# fpga-bank0.net
KiCad netlist of a schematic drawn in Altium Designer
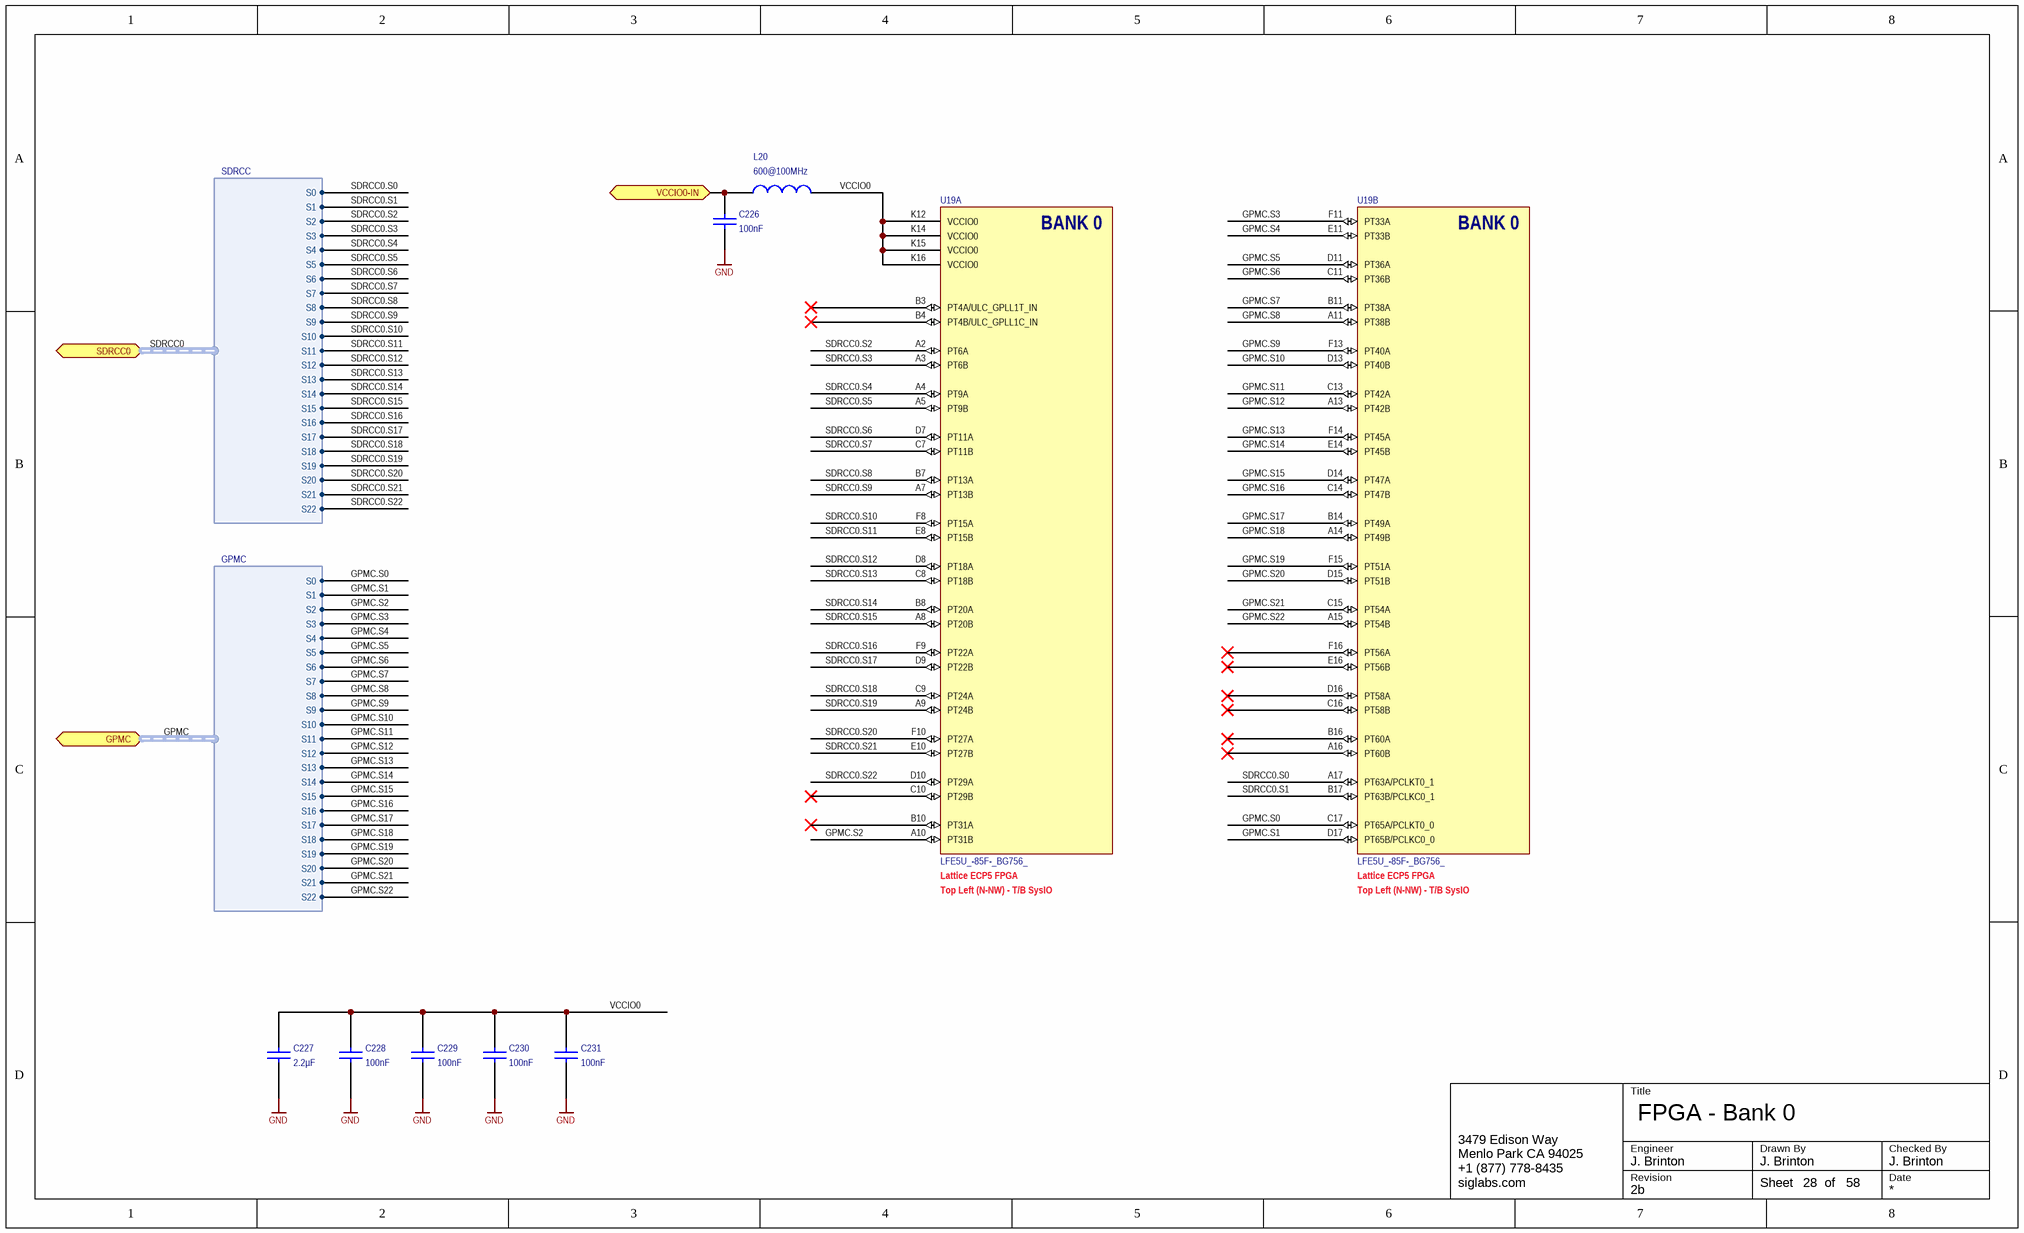
[diagram p0: fpga-bank0.SchDoc]

(export (version "E")
  (design (tool "Eeschema 10.0.6"))
  (components
    (comp (ref "C226")
      (value "100nF")
      (footprint "generic:CAPC1005X56N")
      (description "Ceramic Capacitor 100nF ±10% 16V X7R 0402")
      (fields (field (name "MANUFACTURER") "Murata") (field (name "TOLERANCE") "±10%"))
      (libsource (lib "murata") (part "GRM155R71A104KA01J"))
    )
    (comp (ref "C227")
      (value "2.2µF")
      (footprint "generic:CAPC1608X90N")
      (description "Ceramic Capacitor 2.2uF ±10% 10V X7R 0603")
      (fields (field (name "MANUFACTURER") "Murata") (field (name "TOLERANCE") "±10%"))
      (libsource (lib "murata") (part "GRM188R71A225KE15D"))
    )
    (comp (ref "C228")
      (value "100nF")
      (footprint "generic:CAPC1005X56N")
      (description "Ceramic Capacitor 100nF ±10% 16V X7R 0402")
      (fields (field (name "MANUFACTURER") "Murata") (field (name "TOLERANCE") "±10%"))
      (libsource (lib "murata") (part "GRM155R71A104KA01J"))
    )
    (comp (ref "C229")
      (value "100nF")
      (footprint "generic:CAPC1005X56N")
      (description "Ceramic Capacitor 100nF ±10% 16V X7R 0402")
      (fields (field (name "MANUFACTURER") "Murata") (field (name "TOLERANCE") "±10%"))
      (libsource (lib "murata") (part "GRM155R71A104KA01J"))
    )
    (comp (ref "C230")
      (value "100nF")
      (footprint "generic:CAPC1005X56N")
      (description "Ceramic Capacitor 100nF ±10% 16V X7R 0402")
      (fields (field (name "MANUFACTURER") "Murata") (field (name "TOLERANCE") "±10%"))
      (libsource (lib "murata") (part "GRM155R71A104KA01J"))
    )
    (comp (ref "C231")
      (value "100nF")
      (footprint "generic:CAPC1005X56N")
      (description "Ceramic Capacitor 100nF ±10% 16V X7R 0402")
      (fields (field (name "MANUFACTURER") "Murata") (field (name "TOLERANCE") "±10%"))
      (libsource (lib "murata") (part "GRM155R71A104KA01J"))
    )
    (comp (ref "L20")
      (value "600@100MHz")
      (footprint "0402")
      (description "Ferrite Bead 600-Ohm @ 100MHz 900mA 0402")
      (fields (field (name "MANUFACTURER") "Murata") (field (name "TOLERANCE") "±25%"))
      (libsource (lib "Graviton") (part "IND 0402"))
    )
    (comp (ref "U19")
      (value "LFE5U_-85F-_BG756_")
      (footprint "lattice:caBGA756")
      (description "ECP5 FPGA, 85k LUT, 756-caBGA")
      (fields (field (name "MANUFACTURER") "Lattice Semiconductor"))
      (libsource (lib "lattice") (part "LFE5U_-85F-_BG756_"))
    )
  )
  (nets
    (net (code "3") (name "/GPMC.S0") (class "Default")
      (node (ref "U19") (pin "C17") (pinfunction "PT65A/PCLKT0_0_C17") (pintype "bidirectional"))
    )
    (net (code "4") (name "/GPMC.S1") (class "Default")
      (node (ref "U19") (pin "D17") (pinfunction "PT65B/PCLKC0_0_D17") (pintype "bidirectional"))
    )
    (net (code "5") (name "/GPMC.S2") (class "Default")
      (node (ref "U19") (pin "A10") (pinfunction "PT31B_A10") (pintype "bidirectional"))
    )
    (net (code "6") (name "/GPMC.S3") (class "Default")
      (node (ref "U19") (pin "F11") (pinfunction "PT33A_F11") (pintype "bidirectional"))
    )
    (net (code "7") (name "/GPMC.S4") (class "Default")
      (node (ref "U19") (pin "E11") (pinfunction "PT33B_E11") (pintype "bidirectional"))
    )
    (net (code "8") (name "/GPMC.S5") (class "Default")
      (node (ref "U19") (pin "D11") (pinfunction "PT36A_D11") (pintype "bidirectional"))
    )
    (net (code "9") (name "/GPMC.S6") (class "Default")
      (node (ref "U19") (pin "C11") (pinfunction "PT36B_C11") (pintype "bidirectional"))
    )
    (net (code "10") (name "/GPMC.S7") (class "Default")
      (node (ref "U19") (pin "B11") (pinfunction "PT38A_B11") (pintype "bidirectional"))
    )
    (net (code "11") (name "/GPMC.S8") (class "Default")
      (node (ref "U19") (pin "A11") (pinfunction "PT38B_A11") (pintype "bidirectional"))
    )
    (net (code "12") (name "/GPMC.S9") (class "Default")
      (node (ref "U19") (pin "F13") (pinfunction "PT40A_F13") (pintype "bidirectional"))
    )
    (net (code "13") (name "/GPMC.S10") (class "Default")
      (node (ref "U19") (pin "D13") (pinfunction "PT40B_D13") (pintype "bidirectional"))
    )
    (net (code "14") (name "/GPMC.S11") (class "Default")
      (node (ref "U19") (pin "C13") (pinfunction "PT42A_C13") (pintype "bidirectional"))
    )
    (net (code "15") (name "/GPMC.S12") (class "Default")
      (node (ref "U19") (pin "A13") (pinfunction "PT42B_A13") (pintype "bidirectional"))
    )
    (net (code "16") (name "/GPMC.S13") (class "Default")
      (node (ref "U19") (pin "F14") (pinfunction "PT45A_F14") (pintype "bidirectional"))
    )
    (net (code "17") (name "/GPMC.S14") (class "Default")
      (node (ref "U19") (pin "E14") (pinfunction "PT45B_E14") (pintype "bidirectional"))
    )
    (net (code "18") (name "/GPMC.S15") (class "Default")
      (node (ref "U19") (pin "D14") (pinfunction "PT47A_D14") (pintype "bidirectional"))
    )
    (net (code "19") (name "/GPMC.S16") (class "Default")
      (node (ref "U19") (pin "C14") (pinfunction "PT47B_C14") (pintype "bidirectional"))
    )
    (net (code "20") (name "/GPMC.S17") (class "Default")
      (node (ref "U19") (pin "B14") (pinfunction "PT49A_B14") (pintype "bidirectional"))
    )
    (net (code "21") (name "/GPMC.S18") (class "Default")
      (node (ref "U19") (pin "A14") (pinfunction "PT49B_A14") (pintype "bidirectional"))
    )
    (net (code "22") (name "/GPMC.S19") (class "Default")
      (node (ref "U19") (pin "F15") (pinfunction "PT51A_F15") (pintype "bidirectional"))
    )
    (net (code "23") (name "/GPMC.S20") (class "Default")
      (node (ref "U19") (pin "D15") (pinfunction "PT51B_D15") (pintype "bidirectional"))
    )
    (net (code "24") (name "/GPMC.S21") (class "Default")
      (node (ref "U19") (pin "C15") (pinfunction "PT54A_C15") (pintype "bidirectional"))
    )
    (net (code "25") (name "/GPMC.S22") (class "Default")
      (node (ref "U19") (pin "A15") (pinfunction "PT54B_A15") (pintype "bidirectional"))
    )
    (net (code "27") (name "/SDRCC0.S0") (class "Default")
      (node (ref "U19") (pin "A17") (pinfunction "PT63A/PCLKT0_1_A17") (pintype "bidirectional"))
    )
    (net (code "28") (name "/SDRCC0.S1") (class "Default")
      (node (ref "U19") (pin "B17") (pinfunction "PT63B/PCLKC0_1_B17") (pintype "bidirectional"))
    )
    (net (code "29") (name "/SDRCC0.S2") (class "Default")
      (node (ref "U19") (pin "A2") (pinfunction "PT6A_A2") (pintype "bidirectional"))
    )
    (net (code "30") (name "/SDRCC0.S3") (class "Default")
      (node (ref "U19") (pin "A3") (pinfunction "PT6B_A3") (pintype "bidirectional"))
    )
    (net (code "31") (name "/SDRCC0.S4") (class "Default")
      (node (ref "U19") (pin "A4") (pinfunction "PT9A_A4") (pintype "bidirectional"))
    )
    (net (code "32") (name "/SDRCC0.S5") (class "Default")
      (node (ref "U19") (pin "A5") (pinfunction "PT9B_A5") (pintype "bidirectional"))
    )
    (net (code "33") (name "/SDRCC0.S6") (class "Default")
      (node (ref "U19") (pin "D7") (pinfunction "PT11A_D7") (pintype "bidirectional"))
    )
    (net (code "34") (name "/SDRCC0.S7") (class "Default")
      (node (ref "U19") (pin "C7") (pinfunction "PT11B_C7") (pintype "bidirectional"))
    )
    (net (code "35") (name "/SDRCC0.S8") (class "Default")
      (node (ref "U19") (pin "B7") (pinfunction "PT13A_B7") (pintype "bidirectional"))
    )
    (net (code "36") (name "/SDRCC0.S9") (class "Default")
      (node (ref "U19") (pin "A7") (pinfunction "PT13B_A7") (pintype "bidirectional"))
    )
    (net (code "37") (name "/SDRCC0.S10") (class "Default")
      (node (ref "U19") (pin "F8") (pinfunction "PT15A_F8") (pintype "bidirectional"))
    )
    (net (code "38") (name "/SDRCC0.S11") (class "Default")
      (node (ref "U19") (pin "E8") (pinfunction "PT15B_E8") (pintype "bidirectional"))
    )
    (net (code "39") (name "/SDRCC0.S12") (class "Default")
      (node (ref "U19") (pin "D8") (pinfunction "PT18A_D8") (pintype "bidirectional"))
    )
    (net (code "40") (name "/SDRCC0.S13") (class "Default")
      (node (ref "U19") (pin "C8") (pinfunction "PT18B_C8") (pintype "bidirectional"))
    )
    (net (code "41") (name "/SDRCC0.S14") (class "Default")
      (node (ref "U19") (pin "B8") (pinfunction "PT20A_B8") (pintype "bidirectional"))
    )
    (net (code "42") (name "/SDRCC0.S15") (class "Default")
      (node (ref "U19") (pin "A8") (pinfunction "PT20B_A8") (pintype "bidirectional"))
    )
    (net (code "43") (name "/SDRCC0.S16") (class "Default")
      (node (ref "U19") (pin "F9") (pinfunction "PT22A_F9") (pintype "bidirectional"))
    )
    (net (code "44") (name "/SDRCC0.S17") (class "Default")
      (node (ref "U19") (pin "D9") (pinfunction "PT22B_D9") (pintype "bidirectional"))
    )
    (net (code "45") (name "/SDRCC0.S18") (class "Default")
      (node (ref "U19") (pin "C9") (pinfunction "PT24A_C9") (pintype "bidirectional"))
    )
    (net (code "46") (name "/SDRCC0.S19") (class "Default")
      (node (ref "U19") (pin "A9") (pinfunction "PT24B_A9") (pintype "bidirectional"))
    )
    (net (code "47") (name "/SDRCC0.S20") (class "Default")
      (node (ref "U19") (pin "F10") (pinfunction "PT27A_F10") (pintype "bidirectional"))
    )
    (net (code "48") (name "/SDRCC0.S21") (class "Default")
      (node (ref "U19") (pin "E10") (pinfunction "PT27B_E10") (pintype "bidirectional"))
    )
    (net (code "49") (name "/SDRCC0.S22") (class "Default")
      (node (ref "U19") (pin "D10") (pinfunction "PT29A_D10") (pintype "bidirectional"))
    )
    (net (code "51") (name "/VCCIO0") (class "Default")
      (node (ref "C227") (pin "2") (pinfunction "2_2") (pintype "passive"))
      (node (ref "C228") (pin "2") (pinfunction "2_2") (pintype "passive"))
      (node (ref "C229") (pin "2") (pinfunction "2_2") (pintype "passive"))
      (node (ref "C230") (pin "2") (pinfunction "2_2") (pintype "passive"))
      (node (ref "C231") (pin "2") (pinfunction "2_2") (pintype "passive"))
      (node (ref "L20") (pin "1") (pinfunction "1_1") (pintype "passive"))
      (node (ref "U19") (pin "K12") (pinfunction "VCCIO0_K12") (pintype "power_in"))
      (node (ref "U19") (pin "K14") (pinfunction "VCCIO0_K14") (pintype "power_in"))
      (node (ref "U19") (pin "K15") (pinfunction "VCCIO0_K15") (pintype "power_in"))
      (node (ref "U19") (pin "K16") (pinfunction "VCCIO0_K16") (pintype "power_in"))
    )
    (net (code "52") (name "/VCCIO0-IN") (class "Default")
      (node (ref "C226") (pin "2") (pinfunction "2_2") (pintype "passive"))
      (node (ref "L20") (pin "2") (pinfunction "2_2") (pintype "passive"))
    )
    (net (code "53") (name "GND") (class "Default")
      (node (ref "C226") (pin "1") (pinfunction "1_1") (pintype "passive"))
      (node (ref "C227") (pin "1") (pinfunction "1_1") (pintype "passive"))
      (node (ref "C228") (pin "1") (pinfunction "1_1") (pintype "passive"))
      (node (ref "C229") (pin "1") (pinfunction "1_1") (pintype "passive"))
      (node (ref "C230") (pin "1") (pinfunction "1_1") (pintype "passive"))
      (node (ref "C231") (pin "1") (pinfunction "1_1") (pintype "passive"))
    )
    (net (code "54") (name "unconnected-(U19A-PT4A{slash}ULC_GPLL1T_IN-PadB3)") (class "Default")
      (node (ref "U19") (pin "B3") (pinfunction "PT4A/ULC_GPLL1T_IN_B3") (pintype "bidirectional+no_connect"))
    )
    (net (code "55") (name "unconnected-(U19A-PT4B{slash}ULC_GPLL1C_IN-PadB4)") (class "Default")
      (node (ref "U19") (pin "B4") (pinfunction "PT4B/ULC_GPLL1C_IN_B4") (pintype "bidirectional+no_connect"))
    )
    (net (code "56") (name "unconnected-(U19A-PT29B-PadC10)") (class "Default")
      (node (ref "U19") (pin "C10") (pinfunction "PT29B_C10") (pintype "bidirectional+no_connect"))
    )
    (net (code "57") (name "unconnected-(U19A-PT31A-PadB10)") (class "Default")
      (node (ref "U19") (pin "B10") (pinfunction "PT31A_B10") (pintype "bidirectional+no_connect"))
    )
    (net (code "58") (name "unconnected-(U19B-PT56A-PadF16)") (class "Default")
      (node (ref "U19") (pin "F16") (pinfunction "PT56A_F16") (pintype "bidirectional+no_connect"))
    )
    (net (code "59") (name "unconnected-(U19B-PT56B-PadE16)") (class "Default")
      (node (ref "U19") (pin "E16") (pinfunction "PT56B_E16") (pintype "bidirectional+no_connect"))
    )
    (net (code "60") (name "unconnected-(U19B-PT58A-PadD16)") (class "Default")
      (node (ref "U19") (pin "D16") (pinfunction "PT58A_D16") (pintype "bidirectional+no_connect"))
    )
    (net (code "61") (name "unconnected-(U19B-PT58B-PadC16)") (class "Default")
      (node (ref "U19") (pin "C16") (pinfunction "PT58B_C16") (pintype "bidirectional+no_connect"))
    )
    (net (code "62") (name "unconnected-(U19B-PT60A-PadB16)") (class "Default")
      (node (ref "U19") (pin "B16") (pinfunction "PT60A_B16") (pintype "bidirectional+no_connect"))
    )
    (net (code "63") (name "unconnected-(U19B-PT60B-PadA16)") (class "Default")
      (node (ref "U19") (pin "A16") (pinfunction "PT60B_A16") (pintype "bidirectional+no_connect"))
    )
  )
)
